# base.net
KiCad netlist of a schematic drawn in EAGLE
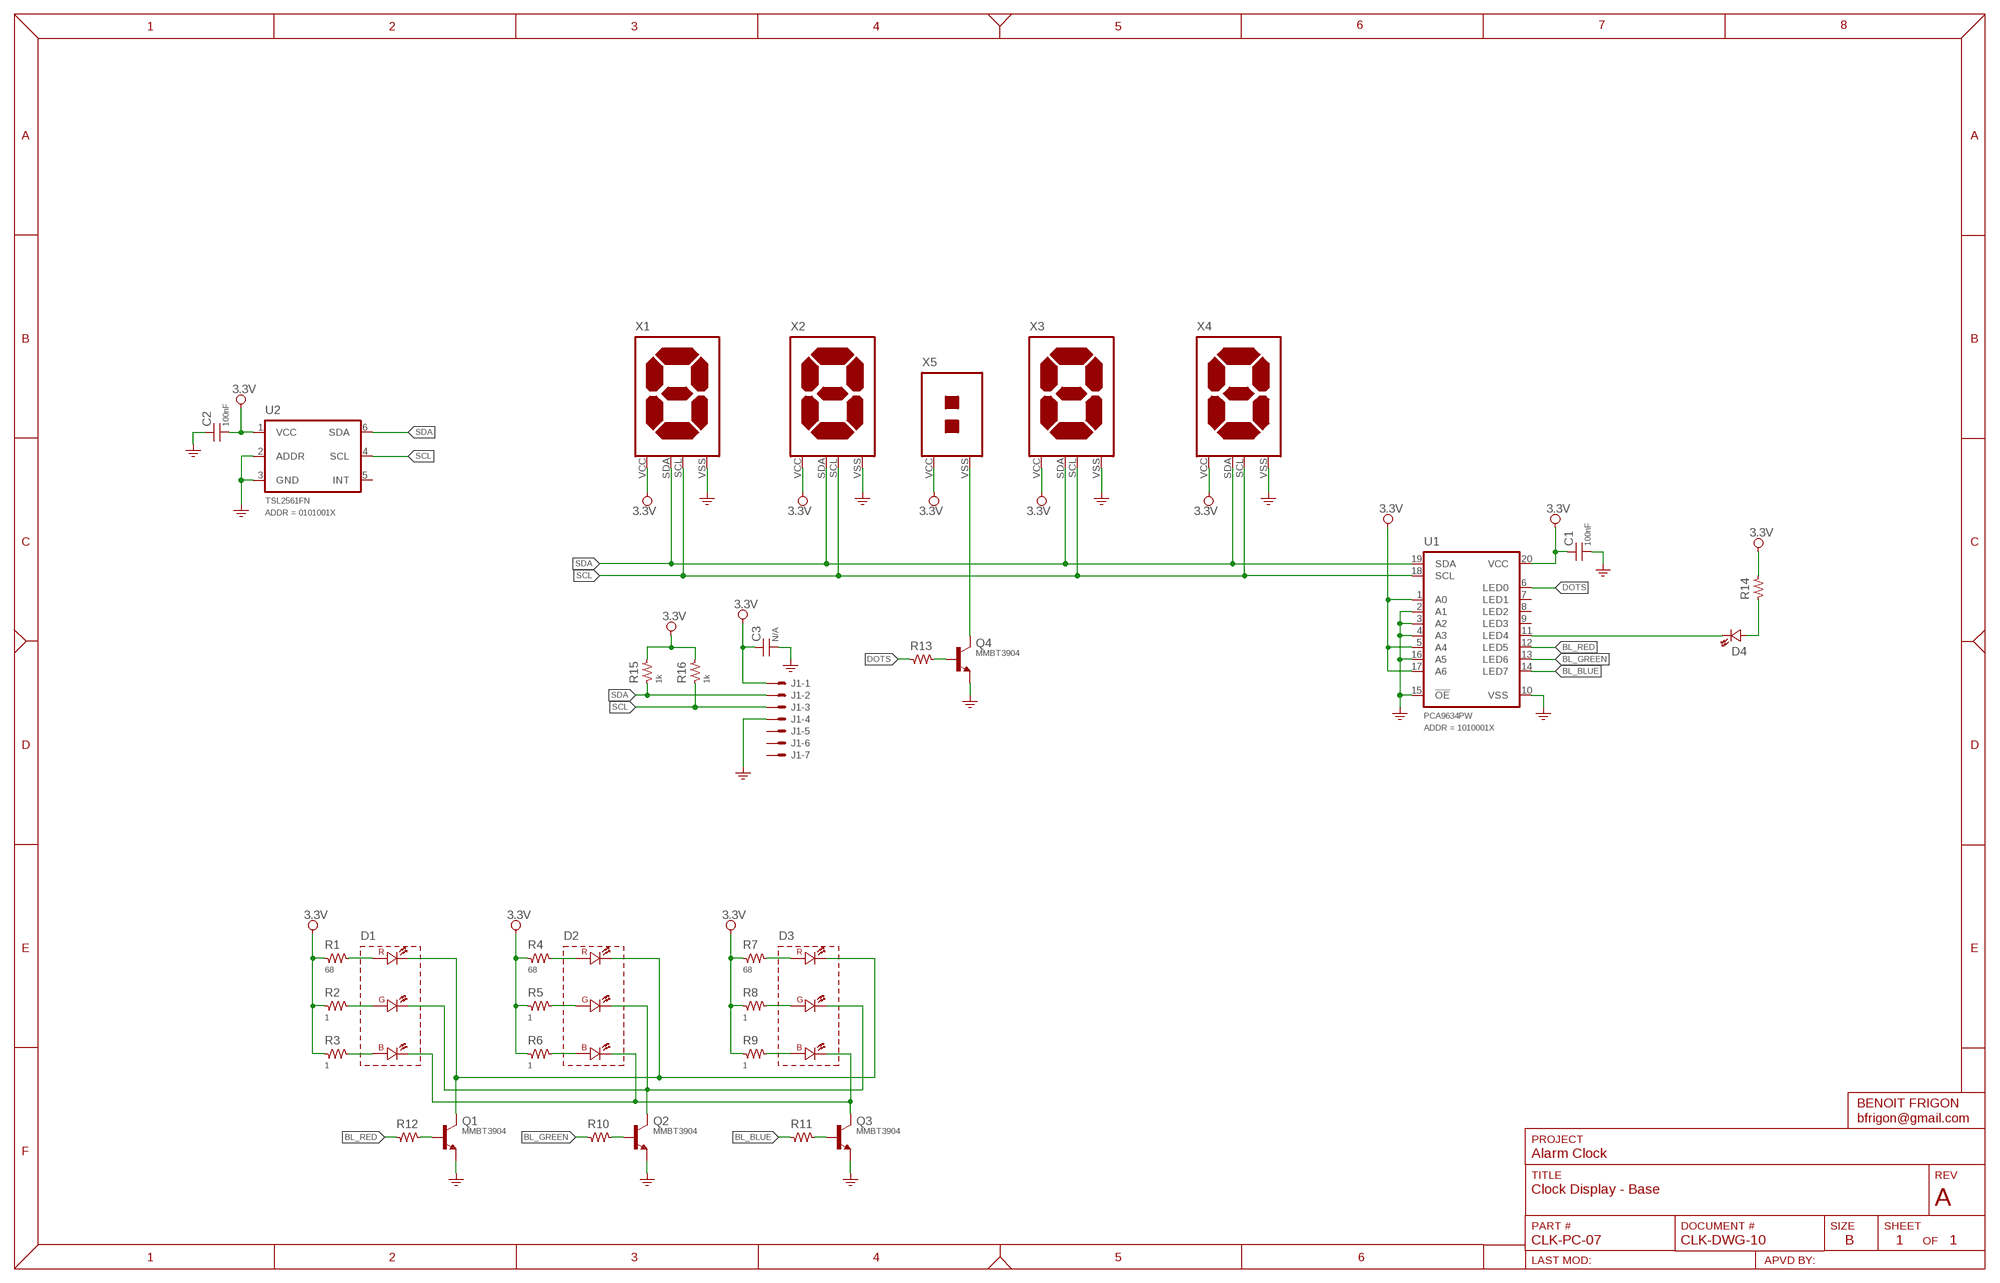
[diagram p0: schematic, sheet 1]

(export (version "E")
  (design (tool "Eeschema 10.0.6"))
  (components
    (comp (ref "C1")
      (value "100nF")
      (footprint "eagle-import:SMD_0603")
      (libsource (lib "eagle-import") (part "CAP-0603"))
    )
    (comp (ref "C2")
      (value "100nF")
      (footprint "eagle-import:SMD_0603")
      (libsource (lib "eagle-import") (part "CAP-0603"))
    )
    (comp (ref "C3")
      (value "N/A")
      (footprint "eagle-import:SMD_0805")
      (description "{DESCRIPTION} - SMT 0805 - {value}")
      (fields (field (name "PACKAGE") "SMT 0805"))
      (libsource (lib "eagle-import") (part "CAP-0805"))
    )
    (comp (ref "D1")
      (value "SMP6-RGB")
      (footprint "eagle-import:LED_RGB_PLCC6")
      (fields (field (name "MFG") "Bivar") (field (name "MFG_1") "BIVAR") (field (name "SKU") "SMP6-RGB"))
      (libsource (lib "eagle-import") (part "SMP6-RGB"))
    )
    (comp (ref "D2")
      (value "SMP6-RGB")
      (footprint "eagle-import:LED_RGB_PLCC6")
      (fields (field (name "MFG") "Bivar"))
      (libsource (lib "eagle-import") (part "SMP6-RGB"))
    )
    (comp (ref "D3")
      (value "SMP6-RGB")
      (footprint "eagle-import:LED_RGB_PLCC6")
      (fields (field (name "MFG") "Bivar"))
      (libsource (lib "eagle-import") (part "SMP6-RGB"))
    )
    (comp (ref "D4")
      (value "{ATTR:COLOR}")
      (footprint "eagle-import:LED_3MM")
      (libsource (lib "eagle-import") (part "LED-T1"))
    )
    (comp (ref "J1")
      (value "SNG-2MM-HEADER-07-V")
      (footprint "eagle-import:DF3X-7P-2DSA")
      (fields
        (field (name "MFG") "Hirose Electronic")
        (field (name "PART_NO") "DF3A-7P-2DSA")
        (field (name "PRICE") "0.37")
        (field (name "SKU") "H2099-ND")
        (field (name "SUPPLIER") "Digi-Key")
      )
      (libsource (lib "eagle-import") (part "SNG-2MM-HEADER-07-V"))
    )
    (comp (ref "Q1")
      (value "MMBT3904")
      (footprint "eagle-import:SOT23")
      (libsource (lib "eagle-import") (part "MMBT3904"))
    )
    (comp (ref "Q2")
      (value "MMBT3904")
      (footprint "eagle-import:SOT23")
      (libsource (lib "eagle-import") (part "MMBT3904"))
    )
    (comp (ref "Q3")
      (value "MMBT3904")
      (footprint "eagle-import:SOT23")
      (libsource (lib "eagle-import") (part "MMBT3904"))
    )
    (comp (ref "Q4")
      (value "MMBT3904")
      (footprint "eagle-import:SOT23")
      (libsource (lib "eagle-import") (part "MMBT3904"))
    )
    (comp (ref "R1")
      (value "68")
      (footprint "eagle-import:SMD_0603")
      (libsource (lib "eagle-import") (part "RES-0603"))
    )
    (comp (ref "R2")
      (value "1")
      (footprint "eagle-import:SMD_0603")
      (description "{DESCRIPTION} - SMT 0603 - {VALUE}")
      (fields (field (name "PACKAGE") "SMT 0603"))
      (libsource (lib "eagle-import") (part "RES-0603"))
    )
    (comp (ref "R3")
      (value "1")
      (footprint "eagle-import:SMD_0603")
      (description "{DESCRIPTION} - SMT 0603 - {VALUE}")
      (fields (field (name "PACKAGE") "SMT 0603"))
      (libsource (lib "eagle-import") (part "RES-0603"))
    )
    (comp (ref "R4")
      (value "68")
      (footprint "eagle-import:SMD_0603")
      (libsource (lib "eagle-import") (part "RES-0603"))
    )
    (comp (ref "R5")
      (value "1")
      (footprint "eagle-import:SMD_0603")
      (description "{DESCRIPTION} - SMT 0603 - {VALUE}")
      (fields (field (name "PACKAGE") "SMT 0603"))
      (libsource (lib "eagle-import") (part "RES-0603"))
    )
    (comp (ref "R6")
      (value "1")
      (footprint "eagle-import:SMD_0603")
      (description "{DESCRIPTION} - SMT 0603 - {VALUE}")
      (fields (field (name "PACKAGE") "SMT 0603"))
      (libsource (lib "eagle-import") (part "RES-0603"))
    )
    (comp (ref "R7")
      (value "68")
      (footprint "eagle-import:SMD_0603")
      (libsource (lib "eagle-import") (part "RES-0603"))
    )
    (comp (ref "R8")
      (value "1")
      (footprint "eagle-import:SMD_0603")
      (description "{DESCRIPTION} - SMT 0603 - {VALUE}")
      (fields (field (name "PACKAGE") "SMT 0603"))
      (libsource (lib "eagle-import") (part "RES-0603"))
    )
    (comp (ref "R9")
      (value "1")
      (footprint "eagle-import:SMD_0603")
      (description "{DESCRIPTION} - SMT 0603 - {VALUE}")
      (fields (field (name "PACKAGE") "SMT 0603"))
      (libsource (lib "eagle-import") (part "RES-0603"))
    )
    (comp (ref "R10")
      (value "RES-0603")
      (footprint "eagle-import:SMD_0603")
      (libsource (lib "eagle-import") (part "RES-0603"))
    )
    (comp (ref "R11")
      (value "RES-0603")
      (footprint "eagle-import:SMD_0603")
      (libsource (lib "eagle-import") (part "RES-0603"))
    )
    (comp (ref "R12")
      (value "RES-0603")
      (footprint "eagle-import:SMD_0603")
      (libsource (lib "eagle-import") (part "RES-0603"))
    )
    (comp (ref "R13")
      (value "RES-0603")
      (footprint "eagle-import:SMD_0603")
      (description "{DESCRIPTION} - SMT 0603 - {VALUE}")
      (fields (field (name "PACKAGE") "SMT 0603"))
      (libsource (lib "eagle-import") (part "RES-0603"))
    )
    (comp (ref "R14")
      (value "RES-0603")
      (footprint "eagle-import:SMD_0603")
      (libsource (lib "eagle-import") (part "RES-0603"))
    )
    (comp (ref "R15")
      (value "1k")
      (footprint "eagle-import:SMD_0603")
      (libsource (lib "eagle-import") (part "RES-0603"))
    )
    (comp (ref "R16")
      (value "1k")
      (footprint "eagle-import:SMD_0603")
      (libsource (lib "eagle-import") (part "RES-0603"))
    )
    (comp (ref "U1")
      (value "PCA9634PW")
      (footprint "eagle-import:TSSOP20")
      (fields (field (name "MFG") "NXP Semiconductors") (field (name "ADDR") "1010001X"))
      (libsource (lib "eagle-import") (part "PCA9634PW"))
    )
    (comp (ref "U2")
      (value "TSL2561FN")
      (footprint "eagle-import:DFN-6")
      (fields (field (name "ADDR") "0101001X"))
      (libsource (lib "eagle-import") (part "TSL2561FN"))
    )
    (comp (ref "X1")
      (value "CLOCK_LED_SEGMENT")
      (footprint "eagle-import:CLOCK_LED_SEGMENT")
      (libsource (lib "eagle-import") (part "CLOCK_LED_SEGMENT"))
    )
    (comp (ref "X2")
      (value "CLOCK_LED_SEGMENT")
      (footprint "eagle-import:CLOCK_LED_SEGMENT")
      (libsource (lib "eagle-import") (part "CLOCK_LED_SEGMENT"))
    )
    (comp (ref "X3")
      (value "CLOCK_LED_SEGMENT")
      (footprint "eagle-import:CLOCK_LED_SEGMENT")
      (libsource (lib "eagle-import") (part "CLOCK_LED_SEGMENT"))
    )
    (comp (ref "X4")
      (value "CLOCK_LED_SEGMENT")
      (footprint "eagle-import:CLOCK_LED_SEGMENT")
      (libsource (lib "eagle-import") (part "CLOCK_LED_SEGMENT"))
    )
    (comp (ref "X5")
      (value "CLOCK_LED_DOTS")
      (footprint "eagle-import:CLOCK_LED_DOTS")
      (libsource (lib "eagle-import") (part "CLOCK_LED_DOTS"))
    )
  )
  (nets
    (net (code "1") (name "3.3V") (class "Default")
      (node (ref "C1") (pin "1") (pinfunction "1_1") (pintype "passive"))
      (node (ref "C2") (pin "2") (pinfunction "2_2") (pintype "passive"))
      (node (ref "C3") (pin "1") (pinfunction "1_1") (pintype "passive"))
      (node (ref "J1") (pin "1") (pinfunction "S_1") (pintype "bidirectional"))
      (node (ref "R1") (pin "1") (pinfunction "1_1") (pintype "passive"))
      (node (ref "R14") (pin "2") (pinfunction "2_2") (pintype "passive"))
      (node (ref "R15") (pin "2") (pinfunction "2_2") (pintype "passive"))
      (node (ref "R16") (pin "2") (pinfunction "2_2") (pintype "passive"))
      (node (ref "R2") (pin "1") (pinfunction "1_1") (pintype "passive"))
      (node (ref "R3") (pin "1") (pinfunction "1_1") (pintype "passive"))
      (node (ref "R4") (pin "1") (pinfunction "1_1") (pintype "passive"))
      (node (ref "R5") (pin "1") (pinfunction "1_1") (pintype "passive"))
      (node (ref "R6") (pin "1") (pinfunction "1_1") (pintype "passive"))
      (node (ref "R7") (pin "1") (pinfunction "1_1") (pintype "passive"))
      (node (ref "R8") (pin "1") (pinfunction "1_1") (pintype "passive"))
      (node (ref "R9") (pin "1") (pinfunction "1_1") (pintype "passive"))
      (node (ref "U1") (pin "1") (pinfunction "A0_1") (pintype "bidirectional"))
      (node (ref "U1") (pin "17") (pinfunction "A6_17") (pintype "bidirectional"))
      (node (ref "U1") (pin "20") (pinfunction "VCC_20") (pintype "bidirectional"))
      (node (ref "U1") (pin "5") (pinfunction "A4_5") (pintype "bidirectional"))
      (node (ref "U2") (pin "1") (pinfunction "VCC_1") (pintype "bidirectional"))
      (node (ref "X1") (pin "VCC") (pinfunction "VCC_VCC") (pintype "bidirectional"))
      (node (ref "X2") (pin "VCC") (pinfunction "VCC_VCC") (pintype "bidirectional"))
      (node (ref "X3") (pin "VCC") (pinfunction "VCC_VCC") (pintype "bidirectional"))
      (node (ref "X4") (pin "VCC") (pinfunction "VCC_VCC") (pintype "bidirectional"))
      (node (ref "X5") (pin "VCC") (pinfunction "VCC_VCC") (pintype "bidirectional"))
    )
    (net (code "2") (name "BL_BLUE") (class "Default")
      (node (ref "R11") (pin "1") (pinfunction "1_1") (pintype "passive"))
      (node (ref "U1") (pin "14") (pinfunction "LED7_14") (pintype "bidirectional"))
    )
    (net (code "3") (name "BL_GREEN") (class "Default")
      (node (ref "R10") (pin "1") (pinfunction "1_1") (pintype "passive"))
      (node (ref "U1") (pin "13") (pinfunction "LED6_13") (pintype "bidirectional"))
    )
    (net (code "4") (name "BL_RED") (class "Default")
      (node (ref "R12") (pin "1") (pinfunction "1_1") (pintype "passive"))
      (node (ref "U1") (pin "12") (pinfunction "LED5_12") (pintype "bidirectional"))
    )
    (net (code "5") (name "DOTS") (class "Default")
      (node (ref "R13") (pin "1") (pinfunction "1_1") (pintype "passive"))
      (node (ref "U1") (pin "6") (pinfunction "LED0_6") (pintype "bidirectional"))
    )
    (net (code "6") (name "GND") (class "Default")
      (node (ref "C1") (pin "2") (pinfunction "2_2") (pintype "passive"))
      (node (ref "C2") (pin "1") (pinfunction "1_1") (pintype "passive"))
      (node (ref "C3") (pin "2") (pinfunction "2_2") (pintype "passive"))
      (node (ref "J1") (pin "4") (pinfunction "S_4") (pintype "bidirectional"))
      (node (ref "Q1") (pin "2") (pinfunction "E_2") (pintype "passive"))
      (node (ref "Q2") (pin "2") (pinfunction "E_2") (pintype "passive"))
      (node (ref "Q3") (pin "2") (pinfunction "E_2") (pintype "passive"))
      (node (ref "Q4") (pin "2") (pinfunction "E_2") (pintype "passive"))
      (node (ref "U1") (pin "10") (pinfunction "VSS_10") (pintype "bidirectional"))
      (node (ref "U1") (pin "15") (pinfunction "~{OE}_15") (pintype "bidirectional"))
      (node (ref "U1") (pin "16") (pinfunction "A5_16") (pintype "bidirectional"))
      (node (ref "U1") (pin "2") (pinfunction "A1_2") (pintype "bidirectional"))
      (node (ref "U1") (pin "3") (pinfunction "A2_3") (pintype "bidirectional"))
      (node (ref "U1") (pin "4") (pinfunction "A3_4") (pintype "bidirectional"))
      (node (ref "U2") (pin "2") (pinfunction "ADDR_2") (pintype "bidirectional"))
      (node (ref "U2") (pin "3") (pinfunction "GND_3") (pintype "bidirectional"))
      (node (ref "X1") (pin "VSS") (pinfunction "VSS_VSS") (pintype "bidirectional"))
      (node (ref "X2") (pin "VSS") (pinfunction "VSS_VSS") (pintype "bidirectional"))
      (node (ref "X3") (pin "VSS") (pinfunction "VSS_VSS") (pintype "bidirectional"))
      (node (ref "X4") (pin "VSS") (pinfunction "VSS_VSS") (pintype "bidirectional"))
    )
    (net (code "7") (name "Net-(D1-BA)") (class "Default")
      (node (ref "D1") (pin "6") (pinfunction "BA_6") (pintype "passive"))
      (node (ref "R3") (pin "2") (pinfunction "2_2") (pintype "passive"))
    )
    (net (code "8") (name "Net-(D1-BK)") (class "Default")
      (node (ref "D1") (pin "5") (pinfunction "BK_5") (pintype "passive"))
      (node (ref "D2") (pin "5") (pinfunction "BK_5") (pintype "passive"))
      (node (ref "D3") (pin "5") (pinfunction "BK_5") (pintype "passive"))
      (node (ref "Q3") (pin "3") (pinfunction "C_3") (pintype "passive"))
    )
    (net (code "9") (name "Net-(D1-GA)") (class "Default")
      (node (ref "D1") (pin "2") (pinfunction "GA_2") (pintype "passive"))
      (node (ref "R2") (pin "2") (pinfunction "2_2") (pintype "passive"))
    )
    (net (code "10") (name "Net-(D1-GK)") (class "Default")
      (node (ref "D1") (pin "1") (pinfunction "GK_1") (pintype "passive"))
      (node (ref "D2") (pin "1") (pinfunction "GK_1") (pintype "passive"))
      (node (ref "D3") (pin "1") (pinfunction "GK_1") (pintype "passive"))
      (node (ref "Q2") (pin "3") (pinfunction "C_3") (pintype "passive"))
    )
    (net (code "11") (name "Net-(D1-RA)") (class "Default")
      (node (ref "D1") (pin "4") (pinfunction "RA_4") (pintype "passive"))
      (node (ref "R1") (pin "2") (pinfunction "2_2") (pintype "passive"))
    )
    (net (code "12") (name "Net-(D1-RK)") (class "Default")
      (node (ref "D1") (pin "3") (pinfunction "RK_3") (pintype "passive"))
      (node (ref "D2") (pin "3") (pinfunction "RK_3") (pintype "passive"))
      (node (ref "D3") (pin "3") (pinfunction "RK_3") (pintype "passive"))
      (node (ref "Q1") (pin "3") (pinfunction "C_3") (pintype "passive"))
    )
    (net (code "13") (name "Net-(D2-BA)") (class "Default")
      (node (ref "D2") (pin "6") (pinfunction "BA_6") (pintype "passive"))
      (node (ref "R6") (pin "2") (pinfunction "2_2") (pintype "passive"))
    )
    (net (code "14") (name "Net-(D2-GA)") (class "Default")
      (node (ref "D2") (pin "2") (pinfunction "GA_2") (pintype "passive"))
      (node (ref "R5") (pin "2") (pinfunction "2_2") (pintype "passive"))
    )
    (net (code "15") (name "Net-(D2-RA)") (class "Default")
      (node (ref "D2") (pin "4") (pinfunction "RA_4") (pintype "passive"))
      (node (ref "R4") (pin "2") (pinfunction "2_2") (pintype "passive"))
    )
    (net (code "16") (name "Net-(D3-BA)") (class "Default")
      (node (ref "D3") (pin "6") (pinfunction "BA_6") (pintype "passive"))
      (node (ref "R9") (pin "2") (pinfunction "2_2") (pintype "passive"))
    )
    (net (code "17") (name "Net-(D3-GA)") (class "Default")
      (node (ref "D3") (pin "2") (pinfunction "GA_2") (pintype "passive"))
      (node (ref "R8") (pin "2") (pinfunction "2_2") (pintype "passive"))
    )
    (net (code "18") (name "Net-(D3-RA)") (class "Default")
      (node (ref "D3") (pin "4") (pinfunction "RA_4") (pintype "passive"))
      (node (ref "R7") (pin "2") (pinfunction "2_2") (pintype "passive"))
    )
    (net (code "19") (name "Net-(D4-PadA)") (class "Default")
      (node (ref "D4") (pin "A") (pinfunction "A_A") (pintype "passive"))
      (node (ref "R14") (pin "1") (pinfunction "1_1") (pintype "passive"))
    )
    (net (code "20") (name "Net-(Q1-B)") (class "Default")
      (node (ref "Q1") (pin "1") (pinfunction "B_1") (pintype "passive"))
      (node (ref "R12") (pin "2") (pinfunction "2_2") (pintype "passive"))
    )
    (net (code "21") (name "Net-(Q2-B)") (class "Default")
      (node (ref "Q2") (pin "1") (pinfunction "B_1") (pintype "passive"))
      (node (ref "R10") (pin "2") (pinfunction "2_2") (pintype "passive"))
    )
    (net (code "22") (name "Net-(Q3-B)") (class "Default")
      (node (ref "Q3") (pin "1") (pinfunction "B_1") (pintype "passive"))
      (node (ref "R11") (pin "2") (pinfunction "2_2") (pintype "passive"))
    )
    (net (code "23") (name "Net-(Q4-B)") (class "Default")
      (node (ref "Q4") (pin "1") (pinfunction "B_1") (pintype "passive"))
      (node (ref "R13") (pin "2") (pinfunction "2_2") (pintype "passive"))
    )
    (net (code "24") (name "Net-(Q4-C)") (class "Default")
      (node (ref "Q4") (pin "3") (pinfunction "C_3") (pintype "passive"))
      (node (ref "X5") (pin "VSS") (pinfunction "VSS_VSS") (pintype "bidirectional"))
    )
    (net (code "25") (name "Net-(U1-LED4)") (class "Default")
      (node (ref "D4") (pin "K") (pinfunction "K_K") (pintype "passive"))
      (node (ref "U1") (pin "11") (pinfunction "LED4_11") (pintype "bidirectional"))
    )
    (net (code "26") (name "SCL") (class "Default")
      (node (ref "J1") (pin "3") (pinfunction "S_3") (pintype "bidirectional"))
      (node (ref "R16") (pin "1") (pinfunction "1_1") (pintype "passive"))
      (node (ref "U1") (pin "18") (pinfunction "SCL_18") (pintype "bidirectional"))
      (node (ref "U2") (pin "4") (pinfunction "SCL_4") (pintype "bidirectional"))
      (node (ref "X1") (pin "SCL") (pinfunction "SCL_SCL") (pintype "bidirectional"))
      (node (ref "X2") (pin "SCL") (pinfunction "SCL_SCL") (pintype "bidirectional"))
      (node (ref "X3") (pin "SCL") (pinfunction "SCL_SCL") (pintype "bidirectional"))
      (node (ref "X4") (pin "SCL") (pinfunction "SCL_SCL") (pintype "bidirectional"))
    )
    (net (code "27") (name "SDA") (class "Default")
      (node (ref "J1") (pin "2") (pinfunction "S_2") (pintype "bidirectional"))
      (node (ref "R15") (pin "1") (pinfunction "1_1") (pintype "passive"))
      (node (ref "U1") (pin "19") (pinfunction "SDA_19") (pintype "bidirectional"))
      (node (ref "U2") (pin "6") (pinfunction "SDA_6") (pintype "bidirectional"))
      (node (ref "X1") (pin "SDA") (pinfunction "SDA_SDA") (pintype "bidirectional"))
      (node (ref "X2") (pin "SDA") (pinfunction "SDA_SDA") (pintype "bidirectional"))
      (node (ref "X3") (pin "SDA") (pinfunction "SDA_SDA") (pintype "bidirectional"))
      (node (ref "X4") (pin "SDA") (pinfunction "SDA_SDA") (pintype "bidirectional"))
    )
    (net (code "28") (name "unconnected-(J1E-S-Pad5)") (class "Default")
      (node (ref "J1") (pin "5") (pinfunction "S_5") (pintype "bidirectional"))
    )
    (net (code "29") (name "unconnected-(J1F-S-Pad6)") (class "Default")
      (node (ref "J1") (pin "6") (pinfunction "S_6") (pintype "bidirectional"))
    )
    (net (code "30") (name "unconnected-(J1G-S-Pad7)") (class "Default")
      (node (ref "J1") (pin "7") (pinfunction "S_7") (pintype "bidirectional"))
    )
    (net (code "31") (name "unconnected-(U1-LED1-Pad7)") (class "Default")
      (node (ref "U1") (pin "7") (pinfunction "LED1_7") (pintype "bidirectional"))
    )
    (net (code "32") (name "unconnected-(U1-LED2-Pad8)") (class "Default")
      (node (ref "U1") (pin "8") (pinfunction "LED2_8") (pintype "bidirectional"))
    )
    (net (code "33") (name "unconnected-(U1-LED3-Pad9)") (class "Default")
      (node (ref "U1") (pin "9") (pinfunction "LED3_9") (pintype "bidirectional"))
    )
    (net (code "34") (name "unconnected-(U2-INT-Pad5)") (class "Default")
      (node (ref "U2") (pin "5") (pinfunction "INT_5") (pintype "bidirectional"))
    )
  )
)
